# 4_cpu_alu.net
KiCad netlist of a schematic drawn in EAGLE
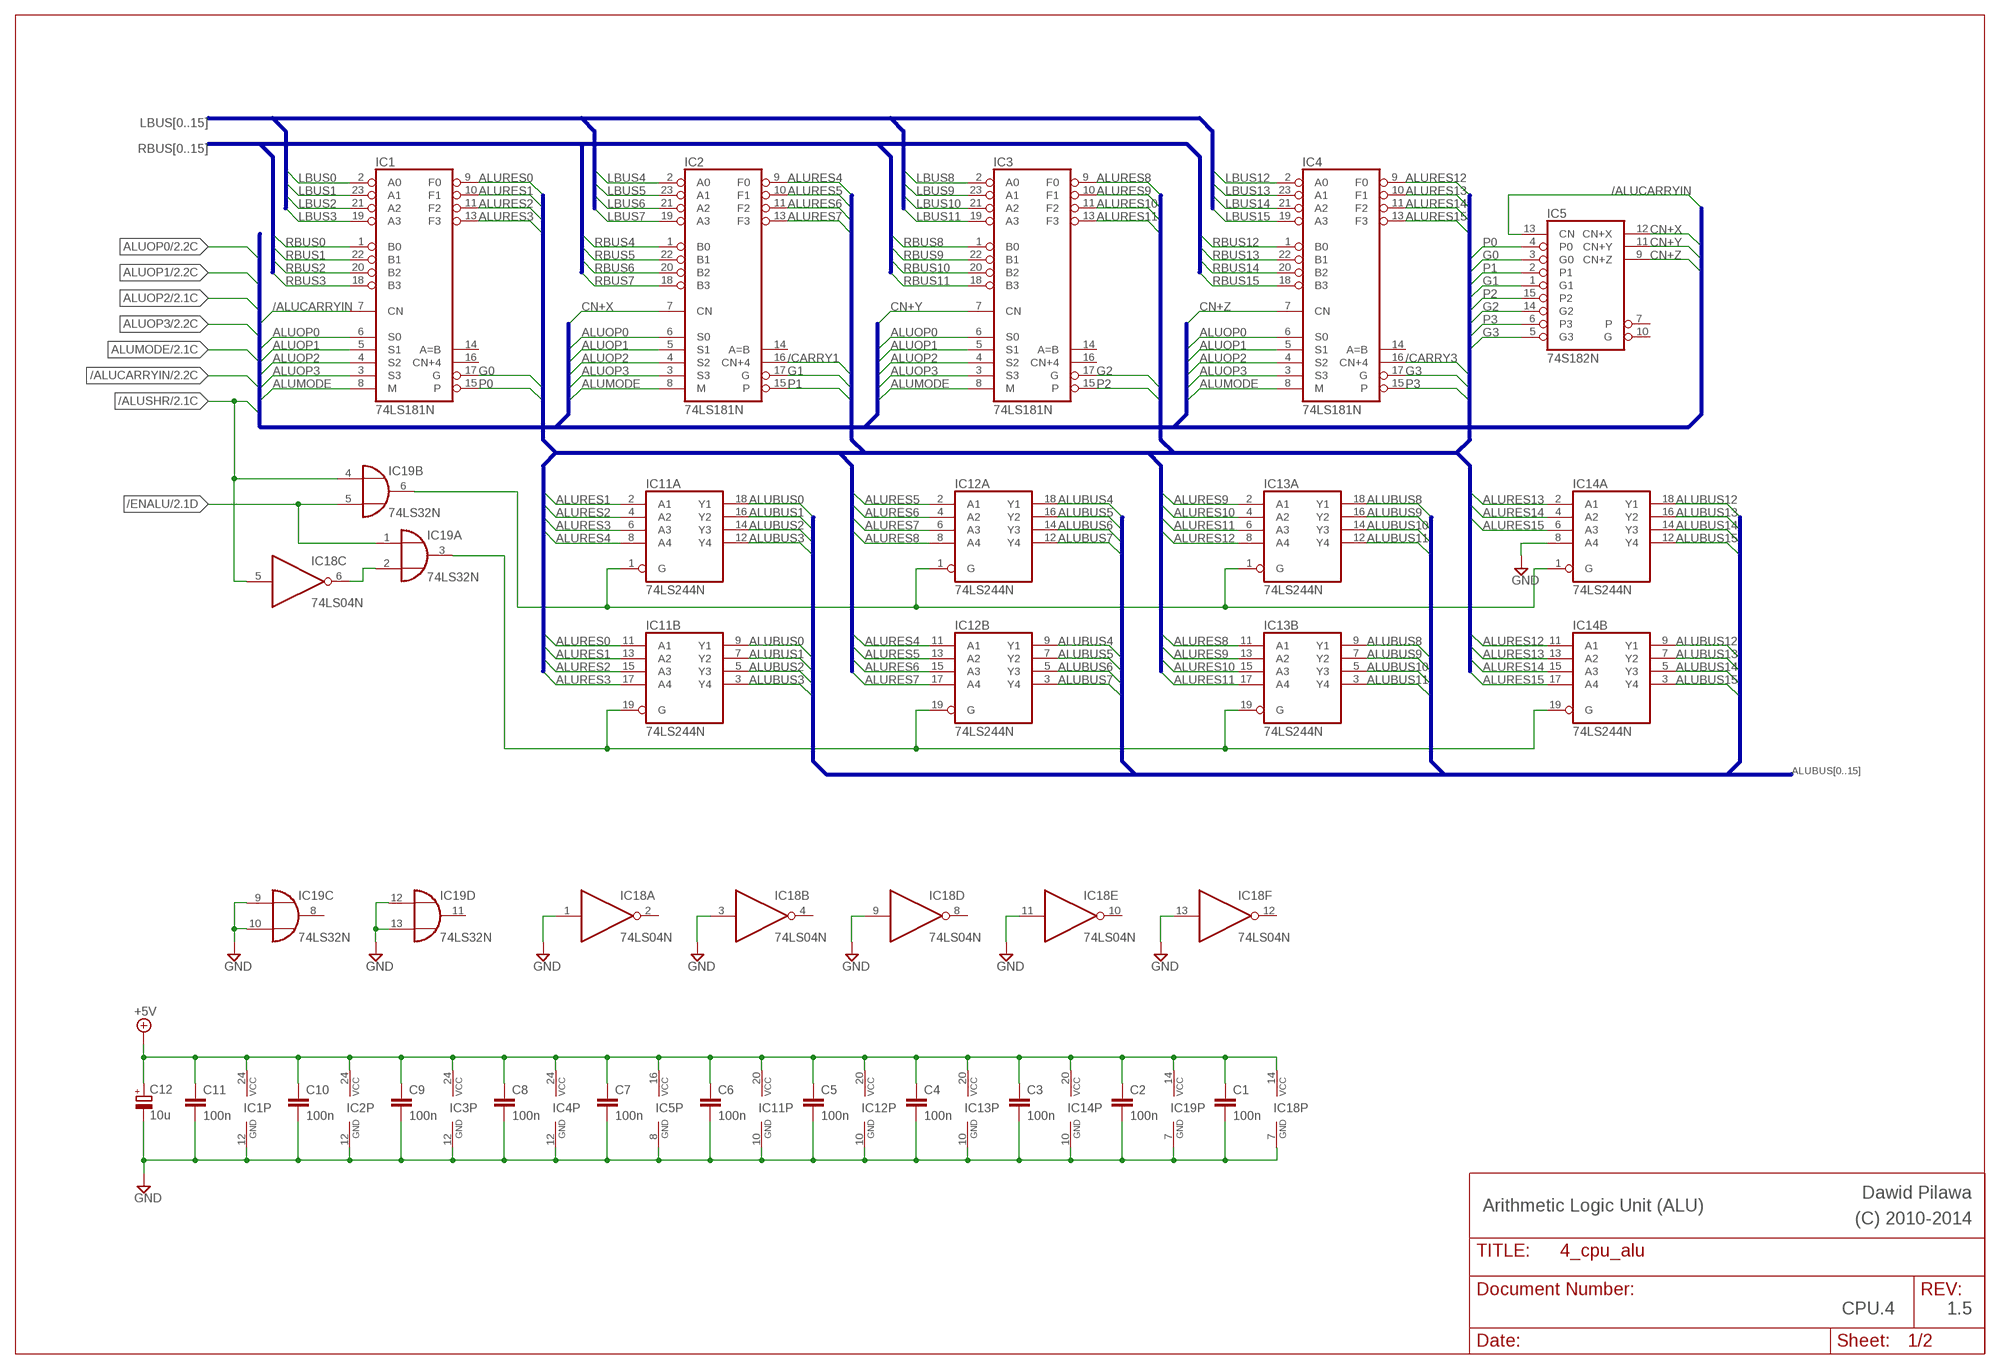
[diagram p0: schematic, sheet 1]
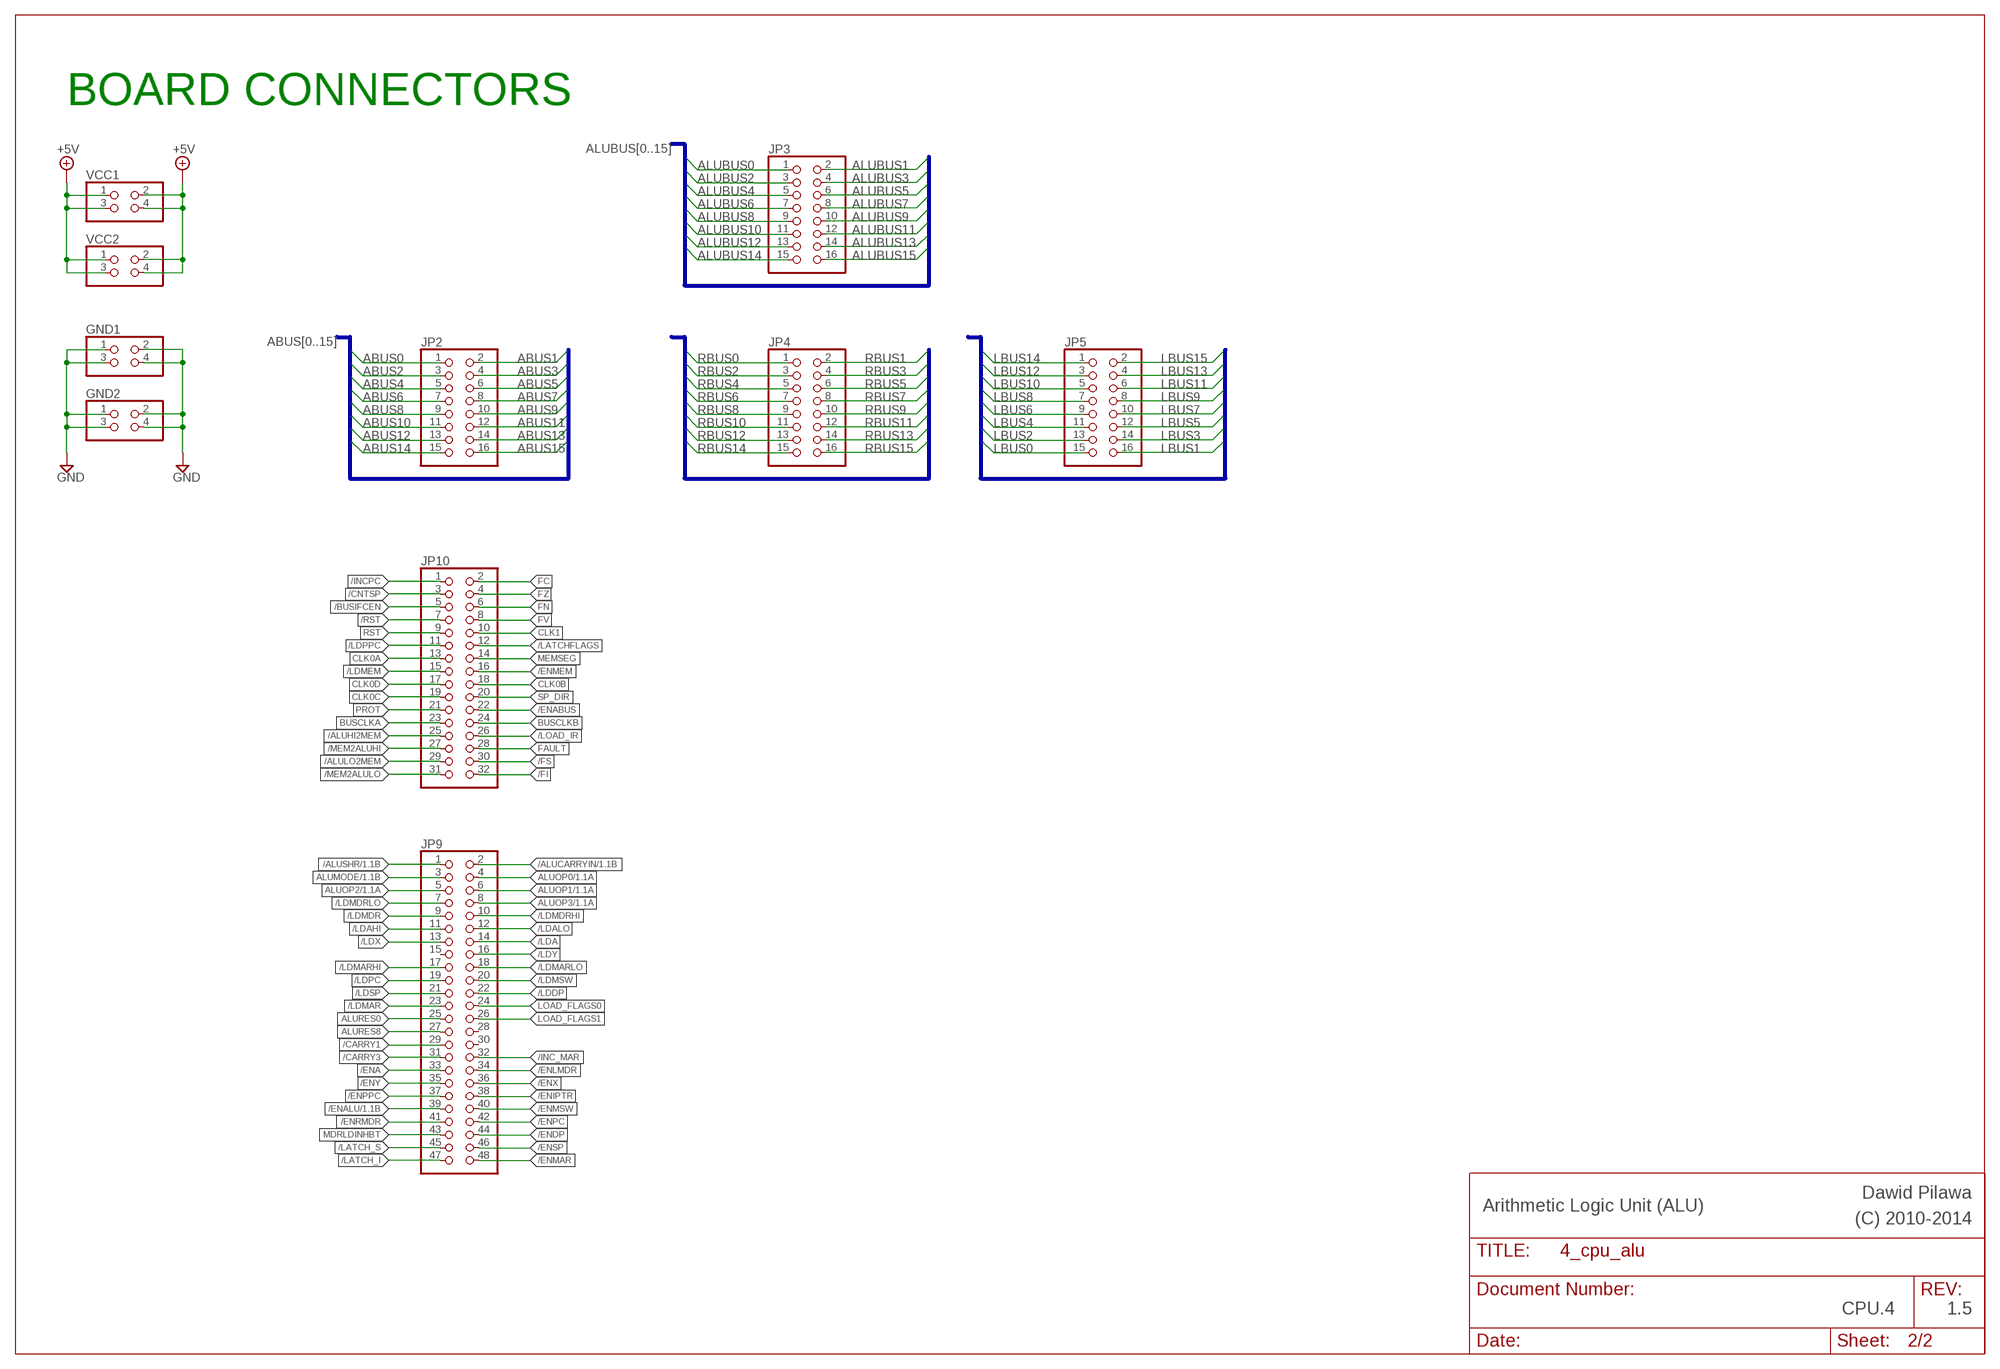
[diagram p1: schematic, sheet 2]

(export (version "E")
  (design (tool "Eeschema 10.0.6"))
  (components
    (comp (ref "GND1")
      (value "PINHD-2X2")
      (footprint "eagle-import:2X02")
      (libsource (lib "eagle-import") (part "PINHD-2X2"))
    )
    (comp (ref "GND2")
      (value "PINHD-2X2")
      (footprint "eagle-import:2X02")
      (libsource (lib "eagle-import") (part "PINHD-2X2"))
    )
    (comp (ref "JP2")
      (value "PINHD-2X8")
      (footprint "eagle-import:2X08")
      (libsource (lib "eagle-import") (part "PINHD-2X8"))
    )
    (comp (ref "JP3")
      (value "PINHD-2X8")
      (footprint "eagle-import:2X08")
      (libsource (lib "eagle-import") (part "PINHD-2X8"))
    )
    (comp (ref "JP4")
      (value "PINHD-2X8")
      (footprint "eagle-import:2X08")
      (libsource (lib "eagle-import") (part "PINHD-2X8"))
    )
    (comp (ref "JP5")
      (value "PINHD-2X8")
      (footprint "eagle-import:2X08")
      (libsource (lib "eagle-import") (part "PINHD-2X8"))
    )
    (comp (ref "JP9")
      (value "PINHD-2X24")
      (footprint "eagle-import:2X24")
      (libsource (lib "eagle-import") (part "PINHD-2X24"))
    )
    (comp (ref "JP10")
      (value "PINHD-2X16")
      (footprint "eagle-import:2X16")
      (libsource (lib "eagle-import") (part "PINHD-2X16"))
    )
    (comp (ref "VCC1")
      (value "PINHD-2X2")
      (footprint "eagle-import:2X02")
      (libsource (lib "eagle-import") (part "PINHD-2X2"))
    )
    (comp (ref "VCC2")
      (value "PINHD-2X2")
      (footprint "eagle-import:2X02")
      (libsource (lib "eagle-import") (part "PINHD-2X2"))
    )
    (comp (ref "C1")
      (value "100n")
      (footprint "eagle-import:C050-024X044")
      (libsource (lib "eagle-import") (part "C-EU050-024X044"))
    )
    (comp (ref "C2")
      (value "100n")
      (footprint "eagle-import:C050-024X044")
      (libsource (lib "eagle-import") (part "C-EU050-024X044"))
    )
    (comp (ref "C3")
      (value "100n")
      (footprint "eagle-import:C050-024X044")
      (libsource (lib "eagle-import") (part "C-EU050-024X044"))
    )
    (comp (ref "C4")
      (value "100n")
      (footprint "eagle-import:C050-024X044")
      (libsource (lib "eagle-import") (part "C-EU050-024X044"))
    )
    (comp (ref "C5")
      (value "100n")
      (footprint "eagle-import:C050-024X044")
      (libsource (lib "eagle-import") (part "C-EU050-024X044"))
    )
    (comp (ref "C6")
      (value "100n")
      (footprint "eagle-import:C050-024X044")
      (libsource (lib "eagle-import") (part "C-EU050-024X044"))
    )
    (comp (ref "C7")
      (value "100n")
      (footprint "eagle-import:C050-024X044")
      (libsource (lib "eagle-import") (part "C-EU050-024X044"))
    )
    (comp (ref "C8")
      (value "100n")
      (footprint "eagle-import:C050-024X044")
      (libsource (lib "eagle-import") (part "C-EU050-024X044"))
    )
    (comp (ref "C9")
      (value "100n")
      (footprint "eagle-import:C050-024X044")
      (libsource (lib "eagle-import") (part "C-EU050-024X044"))
    )
    (comp (ref "C10")
      (value "100n")
      (footprint "eagle-import:C050-024X044")
      (libsource (lib "eagle-import") (part "C-EU050-024X044"))
    )
    (comp (ref "C11")
      (value "100n")
      (footprint "eagle-import:C050-024X044")
      (libsource (lib "eagle-import") (part "C-EU050-024X044"))
    )
    (comp (ref "C12")
      (value "10u")
      (footprint "eagle-import:E2,5-6")
      (libsource (lib "eagle-import") (part "CPOL-EUE2.5-6"))
    )
    (comp (ref "IC1")
      (value "74LS181N")
      (footprint "eagle-import:DIL24-6")
      (libsource (lib "eagle-import") (part "74181NLS"))
    )
    (comp (ref "IC2")
      (value "74LS181N")
      (footprint "eagle-import:DIL24-6")
      (libsource (lib "eagle-import") (part "74181NLS"))
    )
    (comp (ref "IC3")
      (value "74LS181N")
      (footprint "eagle-import:DIL24-6")
      (libsource (lib "eagle-import") (part "74181NLS"))
    )
    (comp (ref "IC4")
      (value "74LS181N")
      (footprint "eagle-import:DIL24-6")
      (libsource (lib "eagle-import") (part "74181NLS"))
    )
    (comp (ref "IC5")
      (value "74S182N")
      (footprint "eagle-import:DIL16")
      (libsource (lib "eagle-import") (part "74182NS"))
    )
    (comp (ref "IC11")
      (value "74LS244N")
      (footprint "eagle-import:DIL20")
      (libsource (lib "eagle-import") (part "74244NLS"))
    )
    (comp (ref "IC12")
      (value "74LS244N")
      (footprint "eagle-import:DIL20")
      (libsource (lib "eagle-import") (part "74244NLS"))
    )
    (comp (ref "IC13")
      (value "74LS244N")
      (footprint "eagle-import:DIL20")
      (libsource (lib "eagle-import") (part "74244NLS"))
    )
    (comp (ref "IC14")
      (value "74LS244N")
      (footprint "eagle-import:DIL20")
      (libsource (lib "eagle-import") (part "74244NLS"))
    )
    (comp (ref "IC18")
      (value "74LS04N")
      (footprint "eagle-import:DIL14")
      (libsource (lib "eagle-import") (part "7404NLS"))
    )
    (comp (ref "IC19")
      (value "74LS32N")
      (footprint "eagle-import:DIL14")
      (libsource (lib "eagle-import") (part "7432NLS"))
    )
  )
  (nets
    (net (code "1") (name "+5V") (class "Default")
      (node (ref "C1") (pin "1") (pinfunction "1_1") (pintype "passive"))
      (node (ref "C10") (pin "1") (pinfunction "1_1") (pintype "passive"))
      (node (ref "C11") (pin "1") (pinfunction "1_1") (pintype "passive"))
      (node (ref "C12") (pin "+") (pinfunction "+_+") (pintype "passive"))
      (node (ref "C2") (pin "1") (pinfunction "1_1") (pintype "passive"))
      (node (ref "C3") (pin "1") (pinfunction "1_1") (pintype "passive"))
      (node (ref "C4") (pin "1") (pinfunction "1_1") (pintype "passive"))
      (node (ref "C5") (pin "1") (pinfunction "1_1") (pintype "passive"))
      (node (ref "C6") (pin "1") (pinfunction "1_1") (pintype "passive"))
      (node (ref "C7") (pin "1") (pinfunction "1_1") (pintype "passive"))
      (node (ref "C8") (pin "1") (pinfunction "1_1") (pintype "passive"))
      (node (ref "C9") (pin "1") (pinfunction "1_1") (pintype "passive"))
      (node (ref "IC1") (pin "24") (pinfunction "VCC_24") (pintype "power_in"))
      (node (ref "IC11") (pin "20") (pinfunction "VCC_20") (pintype "power_in"))
      (node (ref "IC12") (pin "20") (pinfunction "VCC_20") (pintype "power_in"))
      (node (ref "IC13") (pin "20") (pinfunction "VCC_20") (pintype "power_in"))
      (node (ref "IC14") (pin "20") (pinfunction "VCC_20") (pintype "power_in"))
      (node (ref "IC18") (pin "14") (pinfunction "VCC_14") (pintype "power_in"))
      (node (ref "IC19") (pin "14") (pinfunction "VCC_14") (pintype "power_in"))
      (node (ref "IC2") (pin "24") (pinfunction "VCC_24") (pintype "power_in"))
      (node (ref "IC3") (pin "24") (pinfunction "VCC_24") (pintype "power_in"))
      (node (ref "IC4") (pin "24") (pinfunction "VCC_24") (pintype "power_in"))
      (node (ref "IC5") (pin "16") (pinfunction "VCC_16") (pintype "power_in"))
      (node (ref "VCC1") (pin "1") (pinfunction "1_1") (pintype "passive"))
      (node (ref "VCC1") (pin "2") (pinfunction "2_2") (pintype "passive"))
      (node (ref "VCC1") (pin "3") (pinfunction "3_3") (pintype "passive"))
      (node (ref "VCC1") (pin "4") (pinfunction "4_4") (pintype "passive"))
      (node (ref "VCC2") (pin "1") (pinfunction "1_1") (pintype "passive"))
      (node (ref "VCC2") (pin "2") (pinfunction "2_2") (pintype "passive"))
      (node (ref "VCC2") (pin "3") (pinfunction "3_3") (pintype "passive"))
      (node (ref "VCC2") (pin "4") (pinfunction "4_4") (pintype "passive"))
    )
    (net (code "8") (name "ABUS0") (class "Default")
      (node (ref "JP2") (pin "1") (pinfunction "1_1") (pintype "passive"))
    )
    (net (code "9") (name "ABUS1") (class "Default")
      (node (ref "JP2") (pin "2") (pinfunction "2_2") (pintype "passive"))
    )
    (net (code "10") (name "ABUS2") (class "Default")
      (node (ref "JP2") (pin "3") (pinfunction "3_3") (pintype "passive"))
    )
    (net (code "11") (name "ABUS3") (class "Default")
      (node (ref "JP2") (pin "4") (pinfunction "4_4") (pintype "passive"))
    )
    (net (code "12") (name "ABUS4") (class "Default")
      (node (ref "JP2") (pin "5") (pinfunction "5_5") (pintype "passive"))
    )
    (net (code "13") (name "ABUS5") (class "Default")
      (node (ref "JP2") (pin "6") (pinfunction "6_6") (pintype "passive"))
    )
    (net (code "14") (name "ABUS6") (class "Default")
      (node (ref "JP2") (pin "7") (pinfunction "7_7") (pintype "passive"))
    )
    (net (code "15") (name "ABUS7") (class "Default")
      (node (ref "JP2") (pin "8") (pinfunction "8_8") (pintype "passive"))
    )
    (net (code "16") (name "ABUS8") (class "Default")
      (node (ref "JP2") (pin "9") (pinfunction "9_9") (pintype "passive"))
    )
    (net (code "17") (name "ABUS9") (class "Default")
      (node (ref "JP2") (pin "10") (pinfunction "10_10") (pintype "passive"))
    )
    (net (code "18") (name "ABUS10") (class "Default")
      (node (ref "JP2") (pin "11") (pinfunction "11_11") (pintype "passive"))
    )
    (net (code "19") (name "ABUS11") (class "Default")
      (node (ref "JP2") (pin "12") (pinfunction "12_12") (pintype "passive"))
    )
    (net (code "20") (name "ABUS12") (class "Default")
      (node (ref "JP2") (pin "13") (pinfunction "13_13") (pintype "passive"))
    )
    (net (code "21") (name "ABUS13") (class "Default")
      (node (ref "JP2") (pin "14") (pinfunction "14_14") (pintype "passive"))
    )
    (net (code "22") (name "ABUS14") (class "Default")
      (node (ref "JP2") (pin "15") (pinfunction "15_15") (pintype "passive"))
    )
    (net (code "23") (name "ABUS15") (class "Default")
      (node (ref "JP2") (pin "16") (pinfunction "16_16") (pintype "passive"))
    )
    (net (code "24") (name "ALUBUS0") (class "Default")
      (node (ref "IC11") (pin "18") (pinfunction "Y1_18") (pintype "tri_state"))
      (node (ref "IC11") (pin "9") (pinfunction "Y1_9") (pintype "tri_state"))
      (node (ref "JP3") (pin "1") (pinfunction "1_1") (pintype "passive"))
    )
    (net (code "25") (name "ALUBUS1") (class "Default")
      (node (ref "IC11") (pin "16") (pinfunction "Y2_16") (pintype "tri_state"))
      (node (ref "IC11") (pin "7") (pinfunction "Y2_7") (pintype "tri_state"))
      (node (ref "JP3") (pin "2") (pinfunction "2_2") (pintype "passive"))
    )
    (net (code "26") (name "ALUBUS2") (class "Default")
      (node (ref "IC11") (pin "14") (pinfunction "Y3_14") (pintype "tri_state"))
      (node (ref "IC11") (pin "5") (pinfunction "Y3_5") (pintype "tri_state"))
      (node (ref "JP3") (pin "3") (pinfunction "3_3") (pintype "passive"))
    )
    (net (code "27") (name "ALUBUS3") (class "Default")
      (node (ref "IC11") (pin "12") (pinfunction "Y4_12") (pintype "tri_state"))
      (node (ref "IC11") (pin "3") (pinfunction "Y4_3") (pintype "tri_state"))
      (node (ref "JP3") (pin "4") (pinfunction "4_4") (pintype "passive"))
    )
    (net (code "28") (name "ALUBUS4") (class "Default")
      (node (ref "IC12") (pin "18") (pinfunction "Y1_18") (pintype "tri_state"))
      (node (ref "IC12") (pin "9") (pinfunction "Y1_9") (pintype "tri_state"))
      (node (ref "JP3") (pin "5") (pinfunction "5_5") (pintype "passive"))
    )
    (net (code "29") (name "ALUBUS5") (class "Default")
      (node (ref "IC12") (pin "16") (pinfunction "Y2_16") (pintype "tri_state"))
      (node (ref "IC12") (pin "7") (pinfunction "Y2_7") (pintype "tri_state"))
      (node (ref "JP3") (pin "6") (pinfunction "6_6") (pintype "passive"))
    )
    (net (code "30") (name "ALUBUS6") (class "Default")
      (node (ref "IC12") (pin "14") (pinfunction "Y3_14") (pintype "tri_state"))
      (node (ref "IC12") (pin "5") (pinfunction "Y3_5") (pintype "tri_state"))
      (node (ref "JP3") (pin "7") (pinfunction "7_7") (pintype "passive"))
    )
    (net (code "31") (name "ALUBUS7") (class "Default")
      (node (ref "IC12") (pin "12") (pinfunction "Y4_12") (pintype "tri_state"))
      (node (ref "IC12") (pin "3") (pinfunction "Y4_3") (pintype "tri_state"))
      (node (ref "JP3") (pin "8") (pinfunction "8_8") (pintype "passive"))
    )
    (net (code "32") (name "ALUBUS8") (class "Default")
      (node (ref "IC13") (pin "18") (pinfunction "Y1_18") (pintype "tri_state"))
      (node (ref "IC13") (pin "9") (pinfunction "Y1_9") (pintype "tri_state"))
      (node (ref "JP3") (pin "9") (pinfunction "9_9") (pintype "passive"))
    )
    (net (code "33") (name "ALUBUS9") (class "Default")
      (node (ref "IC13") (pin "16") (pinfunction "Y2_16") (pintype "tri_state"))
      (node (ref "IC13") (pin "7") (pinfunction "Y2_7") (pintype "tri_state"))
      (node (ref "JP3") (pin "10") (pinfunction "10_10") (pintype "passive"))
    )
    (net (code "34") (name "ALUBUS10") (class "Default")
      (node (ref "IC13") (pin "14") (pinfunction "Y3_14") (pintype "tri_state"))
      (node (ref "IC13") (pin "5") (pinfunction "Y3_5") (pintype "tri_state"))
      (node (ref "JP3") (pin "11") (pinfunction "11_11") (pintype "passive"))
    )
    (net (code "35") (name "ALUBUS11") (class "Default")
      (node (ref "IC13") (pin "12") (pinfunction "Y4_12") (pintype "tri_state"))
      (node (ref "IC13") (pin "3") (pinfunction "Y4_3") (pintype "tri_state"))
      (node (ref "JP3") (pin "12") (pinfunction "12_12") (pintype "passive"))
    )
    (net (code "36") (name "ALUBUS12") (class "Default")
      (node (ref "IC14") (pin "18") (pinfunction "Y1_18") (pintype "tri_state"))
      (node (ref "IC14") (pin "9") (pinfunction "Y1_9") (pintype "tri_state"))
      (node (ref "JP3") (pin "13") (pinfunction "13_13") (pintype "passive"))
    )
    (net (code "37") (name "ALUBUS13") (class "Default")
      (node (ref "IC14") (pin "16") (pinfunction "Y2_16") (pintype "tri_state"))
      (node (ref "IC14") (pin "7") (pinfunction "Y2_7") (pintype "tri_state"))
      (node (ref "JP3") (pin "14") (pinfunction "14_14") (pintype "passive"))
    )
    (net (code "38") (name "ALUBUS14") (class "Default")
      (node (ref "IC14") (pin "14") (pinfunction "Y3_14") (pintype "tri_state"))
      (node (ref "IC14") (pin "5") (pinfunction "Y3_5") (pintype "tri_state"))
      (node (ref "JP3") (pin "15") (pinfunction "15_15") (pintype "passive"))
    )
    (net (code "39") (name "ALUBUS15") (class "Default")
      (node (ref "IC14") (pin "12") (pinfunction "Y4_12") (pintype "tri_state"))
      (node (ref "IC14") (pin "3") (pinfunction "Y4_3") (pintype "tri_state"))
      (node (ref "JP3") (pin "16") (pinfunction "16_16") (pintype "passive"))
    )
    (net (code "40") (name "ALUMODE") (class "Default")
      (node (ref "IC1") (pin "8") (pinfunction "M_8") (pintype "input"))
      (node (ref "IC2") (pin "8") (pinfunction "M_8") (pintype "input"))
      (node (ref "IC3") (pin "8") (pinfunction "M_8") (pintype "input"))
      (node (ref "IC4") (pin "8") (pinfunction "M_8") (pintype "input"))
      (node (ref "JP9") (pin "3") (pinfunction "3_3") (pintype "passive"))
    )
    (net (code "41") (name "ALUOP0") (class "Default")
      (node (ref "IC1") (pin "6") (pinfunction "S0_6") (pintype "input"))
      (node (ref "IC2") (pin "6") (pinfunction "S0_6") (pintype "input"))
      (node (ref "IC3") (pin "6") (pinfunction "S0_6") (pintype "input"))
      (node (ref "IC4") (pin "6") (pinfunction "S0_6") (pintype "input"))
      (node (ref "JP9") (pin "4") (pinfunction "4_4") (pintype "passive"))
    )
    (net (code "42") (name "ALUOP1") (class "Default")
      (node (ref "IC1") (pin "5") (pinfunction "S1_5") (pintype "input"))
      (node (ref "IC2") (pin "5") (pinfunction "S1_5") (pintype "input"))
      (node (ref "IC3") (pin "5") (pinfunction "S1_5") (pintype "input"))
      (node (ref "IC4") (pin "5") (pinfunction "S1_5") (pintype "input"))
      (node (ref "JP9") (pin "6") (pinfunction "6_6") (pintype "passive"))
    )
    (net (code "43") (name "ALUOP2") (class "Default")
      (node (ref "IC1") (pin "4") (pinfunction "S2_4") (pintype "input"))
      (node (ref "IC2") (pin "4") (pinfunction "S2_4") (pintype "input"))
      (node (ref "IC3") (pin "4") (pinfunction "S2_4") (pintype "input"))
      (node (ref "IC4") (pin "4") (pinfunction "S2_4") (pintype "input"))
      (node (ref "JP9") (pin "5") (pinfunction "5_5") (pintype "passive"))
    )
    (net (code "44") (name "ALUOP3") (class "Default")
      (node (ref "IC1") (pin "3") (pinfunction "S3_3") (pintype "input"))
      (node (ref "IC2") (pin "3") (pinfunction "S3_3") (pintype "input"))
      (node (ref "IC3") (pin "3") (pinfunction "S3_3") (pintype "input"))
      (node (ref "IC4") (pin "3") (pinfunction "S3_3") (pintype "input"))
      (node (ref "JP9") (pin "8") (pinfunction "8_8") (pintype "passive"))
    )
    (net (code "45") (name "ALURES0") (class "Default")
      (node (ref "IC1") (pin "9") (pinfunction "F0_9") (pintype "output"))
      (node (ref "IC11") (pin "11") (pinfunction "A1_11") (pintype "input"))
      (node (ref "JP9") (pin "25") (pinfunction "25_25") (pintype "passive"))
    )
    (net (code "46") (name "ALURES1") (class "Default")
      (node (ref "IC1") (pin "10") (pinfunction "F1_10") (pintype "output"))
      (node (ref "IC11") (pin "13") (pinfunction "A2_13") (pintype "input"))
      (node (ref "IC11") (pin "2") (pinfunction "A1_2") (pintype "input"))
    )
    (net (code "47") (name "ALURES2") (class "Default")
      (node (ref "IC1") (pin "11") (pinfunction "F2_11") (pintype "output"))
      (node (ref "IC11") (pin "15") (pinfunction "A3_15") (pintype "input"))
      (node (ref "IC11") (pin "4") (pinfunction "A2_4") (pintype "input"))
    )
    (net (code "48") (name "ALURES3") (class "Default")
      (node (ref "IC1") (pin "13") (pinfunction "F3_13") (pintype "output"))
      (node (ref "IC11") (pin "17") (pinfunction "A4_17") (pintype "input"))
      (node (ref "IC11") (pin "6") (pinfunction "A3_6") (pintype "input"))
    )
    (net (code "49") (name "ALURES4") (class "Default")
      (node (ref "IC11") (pin "8") (pinfunction "A4_8") (pintype "input"))
      (node (ref "IC12") (pin "11") (pinfunction "A1_11") (pintype "input"))
      (node (ref "IC2") (pin "9") (pinfunction "F0_9") (pintype "output"))
    )
    (net (code "50") (name "ALURES5") (class "Default")
      (node (ref "IC12") (pin "13") (pinfunction "A2_13") (pintype "input"))
      (node (ref "IC12") (pin "2") (pinfunction "A1_2") (pintype "input"))
      (node (ref "IC2") (pin "10") (pinfunction "F1_10") (pintype "output"))
    )
    (net (code "51") (name "ALURES6") (class "Default")
      (node (ref "IC12") (pin "15") (pinfunction "A3_15") (pintype "input"))
      (node (ref "IC12") (pin "4") (pinfunction "A2_4") (pintype "input"))
      (node (ref "IC2") (pin "11") (pinfunction "F2_11") (pintype "output"))
    )
    (net (code "52") (name "ALURES7") (class "Default")
      (node (ref "IC12") (pin "17") (pinfunction "A4_17") (pintype "input"))
      (node (ref "IC12") (pin "6") (pinfunction "A3_6") (pintype "input"))
      (node (ref "IC2") (pin "13") (pinfunction "F3_13") (pintype "output"))
    )
    (net (code "53") (name "ALURES8") (class "Default")
      (node (ref "IC12") (pin "8") (pinfunction "A4_8") (pintype "input"))
      (node (ref "IC13") (pin "11") (pinfunction "A1_11") (pintype "input"))
      (node (ref "IC3") (pin "9") (pinfunction "F0_9") (pintype "output"))
      (node (ref "JP9") (pin "27") (pinfunction "27_27") (pintype "passive"))
    )
    (net (code "54") (name "ALURES9") (class "Default")
      (node (ref "IC13") (pin "13") (pinfunction "A2_13") (pintype "input"))
      (node (ref "IC13") (pin "2") (pinfunction "A1_2") (pintype "input"))
      (node (ref "IC3") (pin "10") (pinfunction "F1_10") (pintype "output"))
    )
    (net (code "55") (name "ALURES10") (class "Default")
      (node (ref "IC13") (pin "15") (pinfunction "A3_15") (pintype "input"))
      (node (ref "IC13") (pin "4") (pinfunction "A2_4") (pintype "input"))
      (node (ref "IC3") (pin "11") (pinfunction "F2_11") (pintype "output"))
    )
    (net (code "56") (name "ALURES11") (class "Default")
      (node (ref "IC13") (pin "17") (pinfunction "A4_17") (pintype "input"))
      (node (ref "IC13") (pin "6") (pinfunction "A3_6") (pintype "input"))
      (node (ref "IC3") (pin "13") (pinfunction "F3_13") (pintype "output"))
    )
    (net (code "57") (name "ALURES12") (class "Default")
      (node (ref "IC13") (pin "8") (pinfunction "A4_8") (pintype "input"))
      (node (ref "IC14") (pin "11") (pinfunction "A1_11") (pintype "input"))
      (node (ref "IC4") (pin "9") (pinfunction "F0_9") (pintype "output"))
    )
    (net (code "58") (name "ALURES13") (class "Default")
      (node (ref "IC14") (pin "13") (pinfunction "A2_13") (pintype "input"))
      (node (ref "IC14") (pin "2") (pinfunction "A1_2") (pintype "input"))
      (node (ref "IC4") (pin "10") (pinfunction "F1_10") (pintype "output"))
    )
    (net (code "59") (name "ALURES14") (class "Default")
      (node (ref "IC14") (pin "15") (pinfunction "A3_15") (pintype "input"))
      (node (ref "IC14") (pin "4") (pinfunction "A2_4") (pintype "input"))
      (node (ref "IC4") (pin "11") (pinfunction "F2_11") (pintype "output"))
    )
    (net (code "60") (name "ALURES15") (class "Default")
      (node (ref "IC14") (pin "17") (pinfunction "A4_17") (pintype "input"))
      (node (ref "IC14") (pin "6") (pinfunction "A3_6") (pintype "input"))
      (node (ref "IC4") (pin "13") (pinfunction "F3_13") (pintype "output"))
    )
    (net (code "61") (name "BUSCLKA") (class "Default")
      (node (ref "JP10") (pin "23") (pinfunction "23_23") (pintype "passive"))
    )
    (net (code "62") (name "BUSCLKB") (class "Default")
      (node (ref "JP10") (pin "24") (pinfunction "24_24") (pintype "passive"))
    )
    (net (code "63") (name "CLK0A") (class "Default")
      (node (ref "JP10") (pin "13") (pinfunction "13_13") (pintype "passive"))
    )
    (net (code "64") (name "CLK0B") (class "Default")
      (node (ref "JP10") (pin "18") (pinfunction "18_18") (pintype "passive"))
    )
    (net (code "65") (name "CLK0C") (class "Default")
      (node (ref "JP10") (pin "19") (pinfunction "19_19") (pintype "passive"))
    )
    (net (code "66") (name "CLK0D") (class "Default")
      (node (ref "JP10") (pin "17") (pinfunction "17_17") (pintype "passive"))
    )
    (net (code "67") (name "CLK1") (class "Default")
      (node (ref "JP10") (pin "10") (pinfunction "10_10") (pintype "passive"))
    )
    (net (code "68") (name "CN+X") (class "Default")
      (node (ref "IC2") (pin "7") (pinfunction "CN_7") (pintype "input"))
      (node (ref "IC5") (pin "12") (pinfunction "CN+X_12") (pintype "output"))
    )
    (net (code "69") (name "CN+Y") (class "Default")
      (node (ref "IC3") (pin "7") (pinfunction "CN_7") (pintype "input"))
      (node (ref "IC5") (pin "11") (pinfunction "CN+Y_11") (pintype "output"))
    )
    (net (code "70") (name "CN+Z") (class "Default")
      (node (ref "IC4") (pin "7") (pinfunction "CN_7") (pintype "input"))
      (node (ref "IC5") (pin "9") (pinfunction "CN+Z_9") (pintype "output"))
    )
    (net (code "71") (name "FAULT") (class "Default")
      (node (ref "JP10") (pin "28") (pinfunction "28_28") (pintype "passive"))
    )
    (net (code "72") (name "FC") (class "Default")
      (node (ref "JP10") (pin "2") (pinfunction "2_2") (pintype "passive"))
    )
    (net (code "73") (name "FN") (class "Default")
      (node (ref "JP10") (pin "6") (pinfunction "6_6") (pintype "passive"))
    )
    (net (code "74") (name "FV") (class "Default")
      (node (ref "JP10") (pin "8") (pinfunction "8_8") (pintype "passive"))
    )
    (net (code "75") (name "FZ") (class "Default")
      (node (ref "JP10") (pin "4") (pinfunction "4_4") (pintype "passive"))
    )
    (net (code "76") (name "G0") (class "Default")
      (node (ref "IC1") (pin "17") (pinfunction "G_17") (pintype "output"))
      (node (ref "IC5") (pin "3") (pinfunction "G0_3") (pintype "input"))
    )
    (net (code "77") (name "G1") (class "Default")
      (node (ref "IC2") (pin "17") (pinfunction "G_17") (pintype "output"))
      (node (ref "IC5") (pin "1") (pinfunction "G1_1") (pintype "input"))
    )
    (net (code "78") (name "G2") (class "Default")
      (node (ref "IC3") (pin "17") (pinfunction "G_17") (pintype "output"))
      (node (ref "IC5") (pin "14") (pinfunction "G2_14") (pintype "input"))
    )
    (net (code "79") (name "G3") (class "Default")
      (node (ref "IC4") (pin "17") (pinfunction "G_17") (pintype "output"))
      (node (ref "IC5") (pin "5") (pinfunction "G3_5") (pintype "input"))
    )
    (net (code "80") (name "GND") (class "Default")
      (node (ref "C1") (pin "2") (pinfunction "2_2") (pintype "passive"))
      (node (ref "C10") (pin "2") (pinfunction "2_2") (pintype "passive"))
      (node (ref "C11") (pin "2") (pinfunction "2_2") (pintype "passive"))
      (node (ref "C12") (pin "-") (pinfunction "-_-") (pintype "passive"))
      (node (ref "C2") (pin "2") (pinfunction "2_2") (pintype "passive"))
      (node (ref "C3") (pin "2") (pinfunction "2_2") (pintype "passive"))
      (node (ref "C4") (pin "2") (pinfunction "2_2") (pintype "passive"))
      (node (ref "C5") (pin "2") (pinfunction "2_2") (pintype "passive"))
      (node (ref "C6") (pin "2") (pinfunction "2_2") (pintype "passive"))
      (node (ref "C7") (pin "2") (pinfunction "2_2") (pintype "passive"))
      (node (ref "C8") (pin "2") (pinfunction "2_2") (pintype "passive"))
      (node (ref "C9") (pin "2") (pinfunction "2_2") (pintype "passive"))
      (node (ref "GND1") (pin "1") (pinfunction "1_1") (pintype "passive"))
      (node (ref "GND1") (pin "2") (pinfunction "2_2") (pintype "passive"))
      (node (ref "GND1") (pin "3") (pinfunction "3_3") (pintype "passive"))
      (node (ref "GND1") (pin "4") (pinfunction "4_4") (pintype "passive"))
      (node (ref "GND2") (pin "1") (pinfunction "1_1") (pintype "passive"))
      (node (ref "GND2") (pin "2") (pinfunction "2_2") (pintype "passive"))
      (node (ref "GND2") (pin "3") (pinfunction "3_3") (pintype "passive"))
      (node (ref "GND2") (pin "4") (pinfunction "4_4") (pintype "passive"))
      (node (ref "IC1") (pin "12") (pinfunction "GND_12") (pintype "power_in"))
      (node (ref "IC11") (pin "10") (pinfunction "GND_10") (pintype "power_in"))
      (node (ref "IC12") (pin "10") (pinfunction "GND_10") (pintype "power_in"))
      (node (ref "IC13") (pin "10") (pinfunction "GND_10") (pintype "power_in"))
      (node (ref "IC14") (pin "10") (pinfunction "GND_10") (pintype "power_in"))
      (node (ref "IC14") (pin "8") (pinfunction "A4_8") (pintype "input"))
      (node (ref "IC18") (pin "1") (pinfunction "I_1") (pintype "input"))
      (node (ref "IC18") (pin "11") (pinfunction "I_11") (pintype "input"))
      (node (ref "IC18") (pin "13") (pinfunction "I_13") (pintype "input"))
      (node (ref "IC18") (pin "3") (pinfunction "I_3") (pintype "input"))
      (node (ref "IC18") (pin "7") (pinfunction "GND_7") (pintype "power_in"))
      (node (ref "IC18") (pin "9") (pinfunction "I_9") (pintype "input"))
      (node (ref "IC19") (pin "10") (pinfunction "I1_10") (pintype "input"))
      (node (ref "IC19") (pin "12") (pinfunction "I0_12") (pintype "input"))
      (node (ref "IC19") (pin "13") (pinfunction "I1_13") (pintype "input"))
      (node (ref "IC19") (pin "7") (pinfunction "GND_7") (pintype "power_in"))
      (node (ref "IC19") (pin "9") (pinfunction "I0_9") (pintype "input"))
      (node (ref "IC2") (pin "12") (pinfunction "GND_12") (pintype "power_in"))
      (node (ref "IC3") (pin "12") (pinfunction "GND_12") (pintype "power_in"))
      (node (ref "IC4") (pin "12") (pinfunction "GND_12") (pintype "power_in"))
      (node (ref "IC5") (pin "8") (pinfunction "GND_8") (pintype "power_in"))
    )
    (net (code "81") (name "LBUS0") (class "Default")
      (node (ref "IC1") (pin "2") (pinfunction "A0_2") (pintype "input"))
      (node (ref "JP5") (pin "15") (pinfunction "15_15") (pintype "passive"))
    )
    (net (code "82") (name "LBUS1") (class "Default")
      (node (ref "IC1") (pin "23") (pinfunction "A1_23") (pintype "input"))
      (node (ref "JP5") (pin "16") (pinfunction "16_16") (pintype "passive"))
    )
    (net (code "83") (name "LBUS2") (class "Default")
      (node (ref "IC1") (pin "21") (pinfunction "A2_21") (pintype "input"))
      (node (ref "JP5") (pin "13") (pinfunction "13_13") (pintype "passive"))
    )
    (net (code "84") (name "LBUS3") (class "Default")
      (node (ref "IC1") (pin "19") (pinfunction "A3_19") (pintype "input"))
      (node (ref "JP5") (pin "14") (pinfunction "14_14") (pintype "passive"))
    )
    (net (code "85") (name "LBUS4") (class "Default")
      (node (ref "IC2") (pin "2") (pinfunction "A0_2") (pintype "input"))
      (node (ref "JP5") (pin "11") (pinfunction "11_11") (pintype "passive"))
    )
    (net (code "86") (name "LBUS5") (class "Default")
      (node (ref "IC2") (pin "23") (pinfunction "A1_23") (pintype "input"))
      (node (ref "JP5") (pin "12") (pinfunction "12_12") (pintype "passive"))
    )
    (net (code "87") (name "LBUS6") (class "Default")
      (node (ref "IC2") (pin "21") (pinfunction "A2_21") (pintype "input"))
      (node (ref "JP5") (pin "9") (pinfunction "9_9") (pintype "passive"))
    )
    (net (code "88") (name "LBUS7") (class "Default")
      (node (ref "IC2") (pin "19") (pinfunction "A3_19") (pintype "input"))
      (node (ref "JP5") (pin "10") (pinfunction "10_10") (pintype "passive"))
    )
    (net (code "89") (name "LBUS8") (class "Default")
      (node (ref "IC3") (pin "2") (pinfunction "A0_2") (pintype "input"))
      (node (ref "JP5") (pin "7") (pinfunction "7_7") (pintype "passive"))
    )
    (net (code "90") (name "LBUS9") (class "Default")
      (node (ref "IC3") (pin "23") (pinfunction "A1_23") (pintype "input"))
      (node (ref "JP5") (pin "8") (pinfunction "8_8") (pintype "passive"))
    )
    (net (code "91") (name "LBUS10") (class "Default")
      (node (ref "IC3") (pin "21") (pinfunction "A2_21") (pintype "input"))
      (node (ref "JP5") (pin "5") (pinfunction "5_5") (pintype "passive"))
    )
    (net (code "92") (name "LBUS11") (class "Default")
      (node (ref "IC3") (pin "19") (pinfunction "A3_19") (pintype "input"))
      (node (ref "JP5") (pin "6") (pinfunction "6_6") (pintype "passive"))
    )
    (net (code "93") (name "LBUS12") (class "Default")
      (node (ref "IC4") (pin "2") (pinfunction "A0_2") (pintype "input"))
      (node (ref "JP5") (pin "3") (pinfunction "3_3") (pintype "passive"))
    )
    (net (code "94") (name "LBUS13") (class "Default")
      (node (ref "IC4") (pin "23") (pinfunction "A1_23") (pintype "input"))
      (node (ref "JP5") (pin "4") (pinfunction "4_4") (pintype "passive"))
    )
    (net (code "95") (name "LBUS14") (class "Default")
      (node (ref "IC4") (pin "21") (pinfunction "A2_21") (pintype "input"))
      (node (ref "JP5") (pin "1") (pinfunction "1_1") (pintype "passive"))
    )
    (net (code "96") (name "LBUS15") (class "Default")
      (node (ref "IC4") (pin "19") (pinfunction "A3_19") (pintype "input"))
      (node (ref "JP5") (pin "2") (pinfunction "2_2") (pintype "passive"))
    )
    (net (code "97") (name "LOAD_FLAGS0") (class "Default")
      (node (ref "JP9") (pin "24") (pinfunction "24_24") (pintype "passive"))
    )
    (net (code "98") (name "LOAD_FLAGS1") (class "Default")
      (node (ref "JP9") (pin "26") (pinfunction "26_26") (pintype "passive"))
    )
    (net (code "99") (name "MDRLDINHBT") (class "Default")
      (node (ref "JP9") (pin "43") (pinfunction "43_43") (pintype "passive"))
    )
    (net (code "100") (name "MEMSEG") (class "Default")
      (node (ref "JP10") (pin "14") (pinfunction "14_14") (pintype "passive"))
    )
    (net (code "101") (name "Net-(IC11A-G)") (class "Default")
      (node (ref "IC11") (pin "1") (pinfunction "G_1") (pintype "input"))
      (node (ref "IC12") (pin "1") (pinfunction "G_1") (pintype "input"))
      (node (ref "IC13") (pin "1") (pinfunction "G_1") (pintype "input"))
      (node (ref "IC14") (pin "1") (pinfunction "G_1") (pintype "input"))
      (node (ref "IC19") (pin "6") (pinfunction "O_6") (pintype "output"))
    )
    (net (code "102") (name "Net-(IC11B-G)") (class "Default")
      (node (ref "IC11") (pin "19") (pinfunction "G_19") (pintype "input"))
      (node (ref "IC12") (pin "19") (pinfunction "G_19") (pintype "input"))
      (node (ref "IC13") (pin "19") (pinfunction "G_19") (pintype "input"))
      (node (ref "IC14") (pin "19") (pinfunction "G_19") (pintype "input"))
      (node (ref "IC19") (pin "3") (pinfunction "O_3") (pintype "output"))
    )
    (net (code "103") (name "Net-(IC18C-O)") (class "Default")
      (node (ref "IC18") (pin "6") (pinfunction "O_6") (pintype "output"))
      (node (ref "IC19") (pin "2") (pinfunction "I1_2") (pintype "input"))
    )
    (net (code "104") (name "P0") (class "Default")
      (node (ref "IC1") (pin "15") (pinfunction "P_15") (pintype "output"))
      (node (ref "IC5") (pin "4") (pinfunction "P0_4") (pintype "input"))
    )
    (net (code "105") (name "P1") (class "Default")
      (node (ref "IC2") (pin "15") (pinfunction "P_15") (pintype "output"))
      (node (ref "IC5") (pin "2") (pinfunction "P1_2") (pintype "input"))
    )
    (net (code "106") (name "P2") (class "Default")
      (node (ref "IC3") (pin "15") (pinfunction "P_15") (pintype "output"))
      (node (ref "IC5") (pin "15") (pinfunction "P2_15") (pintype "input"))
    )
    (net (code "107") (name "P3") (class "Default")
      (node (ref "IC4") (pin "15") (pinfunction "P_15") (pintype "output"))
      (node (ref "IC5") (pin "6") (pinfunction "P3_6") (pintype "input"))
    )
    (net (code "108") (name "PROT") (class "Default")
      (node (ref "JP10") (pin "21") (pinfunction "21_21") (pintype "passive"))
    )
    (net (code "109") (name "RBUS0") (class "Default")
      (node (ref "IC1") (pin "1") (pinfunction "B0_1") (pintype "input"))
      (node (ref "JP4") (pin "1") (pinfunction "1_1") (pintype "passive"))
    )
    (net (code "110") (name "RBUS1") (class "Default")
      (node (ref "IC1") (pin "22") (pinfunction "B1_22") (pintype "input"))
      (node (ref "JP4") (pin "2") (pinfunction "2_2") (pintype "passive"))
    )
    (net (code "111") (name "RBUS2") (class "Default")
      (node (ref "IC1") (pin "20") (pinfunction "B2_20") (pintype "input"))
      (node (ref "JP4") (pin "3") (pinfunction "3_3") (pintype "passive"))
    )
    (net (code "112") (name "RBUS3") (class "Default")
      (node (ref "IC1") (pin "18") (pinfunction "B3_18") (pintype "input"))
      (node (ref "JP4") (pin "4") (pinfunction "4_4") (pintype "passive"))
    )
    (net (code "113") (name "RBUS4") (class "Default")
      (node (ref "IC2") (pin "1") (pinfunction "B0_1") (pintype "input"))
      (node (ref "JP4") (pin "5") (pinfunction "5_5") (pintype "passive"))
    )
    (net (code "114") (name "RBUS5") (class "Default")
      (node (ref "IC2") (pin "22") (pinfunction "B1_22") (pintype "input"))
      (node (ref "JP4") (pin "6") (pinfunction "6_6") (pintype "passive"))
    )
    (net (code "115") (name "RBUS6") (class "Default")
      (node (ref "IC2") (pin "20") (pinfunction "B2_20") (pintype "input"))
      (node (ref "JP4") (pin "7") (pinfunction "7_7") (pintype "passive"))
    )
    (net (code "116") (name "RBUS7") (class "Default")
      (node (ref "IC2") (pin "18") (pinfunction "B3_18") (pintype "input"))
      (node (ref "JP4") (pin "8") (pinfunction "8_8") (pintype "passive"))
    )
    (net (code "117") (name "RBUS8") (class "Default")
      (node (ref "IC3") (pin "1") (pinfunction "B0_1") (pintype "input"))
      (node (ref "JP4") (pin "9") (pinfunction "9_9") (pintype "passive"))
    )
    (net (code "118") (name "RBUS9") (class "Default")
      (node (ref "IC3") (pin "22") (pinfunction "B1_22") (pintype "input"))
      (node (ref "JP4") (pin "10") (pinfunction "10_10") (pintype "passive"))
    )
    (net (code "119") (name "RBUS10") (class "Default")
      (node (ref "IC3") (pin "20") (pinfunction "B2_20") (pintype "input"))
      (node (ref "JP4") (pin "11") (pinfunction "11_11") (pintype "passive"))
    )
    (net (code "120") (name "RBUS11") (class "Default")
      (node (ref "IC3") (pin "18") (pinfunction "B3_18") (pintype "input"))
      (node (ref "JP4") (pin "12") (pinfunction "12_12") (pintype "passive"))
    )
    (net (code "121") (name "RBUS12") (class "Default")
      (node (ref "IC4") (pin "1") (pinfunction "B0_1") (pintype "input"))
      (node (ref "JP4") (pin "13") (pinfunction "13_13") (pintype "passive"))
    )
    (net (code "122") (name "RBUS13") (class "Default")
      (node (ref "IC4") (pin "22") (pinfunction "B1_22") (pintype "input"))
      (node (ref "JP4") (pin "14") (pinfunction "14_14") (pintype "passive"))
    )
    (net (code "123") (name "RBUS14") (class "Default")
      (node (ref "IC4") (pin "20") (pinfunction "B2_20") (pintype "input"))
      (node (ref "JP4") (pin "15") (pinfunction "15_15") (pintype "passive"))
    )
    (net (code "124") (name "RBUS15") (class "Default")
      (node (ref "IC4") (pin "18") (pinfunction "B3_18") (pintype "input"))
      (node (ref "JP4") (pin "16") (pinfunction "16_16") (pintype "passive"))
    )
    (net (code "125") (name "RST") (class "Default")
      (node (ref "JP10") (pin "9") (pinfunction "9_9") (pintype "passive"))
    )
    (net (code "126") (name "SP_DIR") (class "Default")
      (node (ref "JP10") (pin "20") (pinfunction "20_20") (pintype "passive"))
    )
    (net (code "127") (name "unconnected-(IC1A-A=B-Pad14)") (class "Default")
      (node (ref "IC1") (pin "14") (pinfunction "A=B_14") (pintype "output"))
    )
    (net (code "128") (name "unconnected-(IC1A-CN+4-Pad16)") (class "Default")
      (node (ref "IC1") (pin "16") (pinfunction "CN+4_16") (pintype "output"))
    )
    (net (code "129") (name "unconnected-(IC2A-A=B-Pad14)") (class "Default")
      (node (ref "IC2") (pin "14") (pinfunction "A=B_14") (pintype "output"))
    )
    (net (code "130") (name "unconnected-(IC3A-A=B-Pad14)") (class "Default")
      (node (ref "IC3") (pin "14") (pinfunction "A=B_14") (pintype "output"))
    )
    (net (code "131") (name "unconnected-(IC3A-CN+4-Pad16)") (class "Default")
      (node (ref "IC3") (pin "16") (pinfunction "CN+4_16") (pintype "output"))
    )
    (net (code "132") (name "unconnected-(IC4A-A=B-Pad14)") (class "Default")
      (node (ref "IC4") (pin "14") (pinfunction "A=B_14") (pintype "output"))
    )
    (net (code "133") (name "unconnected-(IC5A-G-Pad10)") (class "Default")
      (node (ref "IC5") (pin "10") (pinfunction "G_10") (pintype "output"))
    )
    (net (code "134") (name "unconnected-(IC5A-P-Pad7)") (class "Default")
      (node (ref "IC5") (pin "7") (pinfunction "P_7") (pintype "output"))
    )
    (net (code "135") (name "unconnected-(IC18A-O-Pad2)") (class "Default")
      (node (ref "IC18") (pin "2") (pinfunction "O_2") (pintype "output"))
    )
    (net (code "136") (name "unconnected-(IC18B-O-Pad4)") (class "Default")
      (node (ref "IC18") (pin "4") (pinfunction "O_4") (pintype "output"))
    )
    (net (code "137") (name "unconnected-(IC18D-O-Pad8)") (class "Default")
      (node (ref "IC18") (pin "8") (pinfunction "O_8") (pintype "output"))
    )
    (net (code "138") (name "unconnected-(IC18E-O-Pad10)") (class "Default")
      (node (ref "IC18") (pin "10") (pinfunction "O_10") (pintype "output"))
    )
    (net (code "139") (name "unconnected-(IC18F-O-Pad12)") (class "Default")
      (node (ref "IC18") (pin "12") (pinfunction "O_12") (pintype "output"))
    )
    (net (code "140") (name "unconnected-(IC19C-O-Pad8)") (class "Default")
      (node (ref "IC19") (pin "8") (pinfunction "O_8") (pintype "output"))
    )
    (net (code "141") (name "unconnected-(IC19D-O-Pad11)") (class "Default")
      (node (ref "IC19") (pin "11") (pinfunction "O_11") (pintype "output"))
    )
    (net (code "142") (name "unconnected-(JP9-Pad15)") (class "Default")
      (node (ref "JP9") (pin "15") (pinfunction "15_15") (pintype "passive"))
    )
    (net (code "143") (name "unconnected-(JP9-Pad28)") (class "Default")
      (node (ref "JP9") (pin "28") (pinfunction "28_28") (pintype "passive"))
    )
    (net (code "144") (name "unconnected-(JP9-Pad30)") (class "Default")
      (node (ref "JP9") (pin "30") (pinfunction "30_30") (pintype "passive"))
    )
    (net (code "145") (name "{slash}ALUCARRYIN") (class "Default")
      (node (ref "IC1") (pin "7") (pinfunction "CN_7") (pintype "input"))
      (node (ref "IC5") (pin "13") (pinfunction "CN_13") (pintype "input"))
      (node (ref "JP9") (pin "2") (pinfunction "2_2") (pintype "passive"))
    )
    (net (code "146") (name "{slash}ALUHI2MEM") (class "Default")
      (node (ref "JP10") (pin "25") (pinfunction "25_25") (pintype "passive"))
    )
    (net (code "147") (name "{slash}ALULO2MEM") (class "Default")
      (node (ref "JP10") (pin "29") (pinfunction "29_29") (pintype "passive"))
    )
    (net (code "148") (name "{slash}ALUSHR") (class "Default")
      (node (ref "IC18") (pin "5") (pinfunction "I_5") (pintype "input"))
      (node (ref "IC19") (pin "4") (pinfunction "I0_4") (pintype "input"))
      (node (ref "JP9") (pin "1") (pinfunction "1_1") (pintype "passive"))
    )
    (net (code "149") (name "{slash}BUSIFCEN") (class "Default")
      (node (ref "JP10") (pin "5") (pinfunction "5_5") (pintype "passive"))
    )
    (net (code "150") (name "{slash}CARRY1") (class "Default")
      (node (ref "IC2") (pin "16") (pinfunction "CN+4_16") (pintype "output"))
      (node (ref "JP9") (pin "29") (pinfunction "29_29") (pintype "passive"))
    )
    (net (code "151") (name "{slash}CARRY3") (class "Default")
      (node (ref "IC4") (pin "16") (pinfunction "CN+4_16") (pintype "output"))
      (node (ref "JP9") (pin "31") (pinfunction "31_31") (pintype "passive"))
    )
    (net (code "152") (name "{slash}CNTSP") (class "Default")
      (node (ref "JP10") (pin "3") (pinfunction "3_3") (pintype "passive"))
    )
    (net (code "153") (name "{slash}ENA") (class "Default")
      (node (ref "JP9") (pin "33") (pinfunction "33_33") (pintype "passive"))
    )
    (net (code "154") (name "{slash}ENABUS") (class "Default")
      (node (ref "JP10") (pin "22") (pinfunction "22_22") (pintype "passive"))
    )
    (net (code "155") (name "{slash}ENALU") (class "Default")
      (node (ref "IC19") (pin "1") (pinfunction "I0_1") (pintype "input"))
      (node (ref "IC19") (pin "5") (pinfunction "I1_5") (pintype "input"))
      (node (ref "JP9") (pin "39") (pinfunction "39_39") (pintype "passive"))
    )
    (net (code "156") (name "{slash}ENDP") (class "Default")
      (node (ref "JP9") (pin "44") (pinfunction "44_44") (pintype "passive"))
    )
    (net (code "157") (name "{slash}ENIPTR") (class "Default")
      (node (ref "JP9") (pin "38") (pinfunction "38_38") (pintype "passive"))
    )
    (net (code "158") (name "{slash}ENLMDR") (class "Default")
      (node (ref "JP9") (pin "34") (pinfunction "34_34") (pintype "passive"))
    )
    (net (code "159") (name "{slash}ENMAR") (class "Default")
      (node (ref "JP9") (pin "48") (pinfunction "48_48") (pintype "passive"))
    )
    (net (code "160") (name "{slash}ENMEM") (class "Default")
      (node (ref "JP10") (pin "16") (pinfunction "16_16") (pintype "passive"))
    )
    (net (code "161") (name "{slash}ENMSW") (class "Default")
      (node (ref "JP9") (pin "40") (pinfunction "40_40") (pintype "passive"))
    )
    (net (code "162") (name "{slash}ENPC") (class "Default")
      (node (ref "JP9") (pin "42") (pinfunction "42_42") (pintype "passive"))
    )
    (net (code "163") (name "{slash}ENPPC") (class "Default")
      (node (ref "JP9") (pin "37") (pinfunction "37_37") (pintype "passive"))
    )
    (net (code "164") (name "{slash}ENRMDR") (class "Default")
      (node (ref "JP9") (pin "41") (pinfunction "41_41") (pintype "passive"))
    )
    (net (code "165") (name "{slash}ENSP") (class "Default")
      (node (ref "JP9") (pin "46") (pinfunction "46_46") (pintype "passive"))
    )
    (net (code "166") (name "{slash}ENX") (class "Default")
      (node (ref "JP9") (pin "36") (pinfunction "36_36") (pintype "passive"))
    )
    (net (code "167") (name "{slash}ENY") (class "Default")
      (node (ref "JP9") (pin "35") (pinfunction "35_35") (pintype "passive"))
    )
    (net (code "168") (name "{slash}FI") (class "Default")
      (node (ref "JP10") (pin "32") (pinfunction "32_32") (pintype "passive"))
    )
    (net (code "169") (name "{slash}FS") (class "Default")
      (node (ref "JP10") (pin "30") (pinfunction "30_30") (pintype "passive"))
    )
    (net (code "170") (name "{slash}INCPC") (class "Default")
      (node (ref "JP10") (pin "1") (pinfunction "1_1") (pintype "passive"))
    )
    (net (code "171") (name "{slash}INC_MAR") (class "Default")
      (node (ref "JP9") (pin "32") (pinfunction "32_32") (pintype "passive"))
    )
    (net (code "172") (name "{slash}LATCHFLAGS") (class "Default")
      (node (ref "JP10") (pin "12") (pinfunction "12_12") (pintype "passive"))
    )
    (net (code "173") (name "{slash}LATCH_I") (class "Default")
      (node (ref "JP9") (pin "47") (pinfunction "47_47") (pintype "passive"))
    )
    (net (code "174") (name "{slash}LATCH_S") (class "Default")
      (node (ref "JP9") (pin "45") (pinfunction "45_45") (pintype "passive"))
    )
    (net (code "175") (name "{slash}LDA") (class "Default")
      (node (ref "JP9") (pin "14") (pinfunction "14_14") (pintype "passive"))
    )
    (net (code "176") (name "{slash}LDAHI") (class "Default")
      (node (ref "JP9") (pin "11") (pinfunction "11_11") (pintype "passive"))
    )
    (net (code "177") (name "{slash}LDALO") (class "Default")
      (node (ref "JP9") (pin "12") (pinfunction "12_12") (pintype "passive"))
    )
    (net (code "178") (name "{slash}LDDP") (class "Default")
      (node (ref "JP9") (pin "22") (pinfunction "22_22") (pintype "passive"))
    )
    (net (code "179") (name "{slash}LDMAR") (class "Default")
      (node (ref "JP9") (pin "23") (pinfunction "23_23") (pintype "passive"))
    )
    (net (code "180") (name "{slash}LDMARHI") (class "Default")
      (node (ref "JP9") (pin "17") (pinfunction "17_17") (pintype "passive"))
    )
    (net (code "181") (name "{slash}LDMARLO") (class "Default")
      (node (ref "JP9") (pin "18") (pinfunction "18_18") (pintype "passive"))
    )
    (net (code "182") (name "{slash}LDMDR") (class "Default")
      (node (ref "JP9") (pin "9") (pinfunction "9_9") (pintype "passive"))
    )
    (net (code "183") (name "{slash}LDMDRHI") (class "Default")
      (node (ref "JP9") (pin "10") (pinfunction "10_10") (pintype "passive"))
    )
    (net (code "184") (name "{slash}LDMDRLO") (class "Default")
      (node (ref "JP9") (pin "7") (pinfunction "7_7") (pintype "passive"))
    )
    (net (code "185") (name "{slash}LDMEM") (class "Default")
      (node (ref "JP10") (pin "15") (pinfunction "15_15") (pintype "passive"))
    )
    (net (code "186") (name "{slash}LDMSW") (class "Default")
      (node (ref "JP9") (pin "20") (pinfunction "20_20") (pintype "passive"))
    )
    (net (code "187") (name "{slash}LDPC") (class "Default")
      (node (ref "JP9") (pin "19") (pinfunction "19_19") (pintype "passive"))
    )
    (net (code "188") (name "{slash}LDPPC") (class "Default")
      (node (ref "JP10") (pin "11") (pinfunction "11_11") (pintype "passive"))
    )
    (net (code "189") (name "{slash}LDSP") (class "Default")
      (node (ref "JP9") (pin "21") (pinfunction "21_21") (pintype "passive"))
    )
    (net (code "190") (name "{slash}LDX") (class "Default")
      (node (ref "JP9") (pin "13") (pinfunction "13_13") (pintype "passive"))
    )
    (net (code "191") (name "{slash}LDY") (class "Default")
      (node (ref "JP9") (pin "16") (pinfunction "16_16") (pintype "passive"))
    )
    (net (code "192") (name "{slash}LOAD_IR") (class "Default")
      (node (ref "JP10") (pin "26") (pinfunction "26_26") (pintype "passive"))
    )
    (net (code "193") (name "{slash}MEM2ALUHI") (class "Default")
      (node (ref "JP10") (pin "27") (pinfunction "27_27") (pintype "passive"))
    )
    (net (code "194") (name "{slash}MEM2ALULO") (class "Default")
      (node (ref "JP10") (pin "31") (pinfunction "31_31") (pintype "passive"))
    )
    (net (code "195") (name "{slash}RST") (class "Default")
      (node (ref "JP10") (pin "7") (pinfunction "7_7") (pintype "passive"))
    )
  )
)
